# TP_IHM_7SEG.net
KiCad netlist of a schematic drawn in Altium Designer
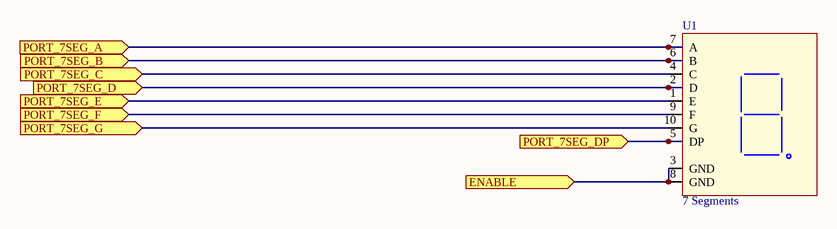
[diagram p0: TP_IHM_7SEG.SchDoc]

(export (version "E")
  (design (tool "Eeschema 10.0.6"))
  (components
    (comp (ref "U1")
      (value "7 Segments")
      (footprint "SA10-21GWA")
      (description "KingBright Led 7 Segments")
      (libsource (lib "TpGiven") (part "SC10-21SRWA"))
    )
  )
  (nets
    (net (code "1") (name "/ENABLE") (class "Default")
      (node (ref "U1") (pin "3") (pinfunction "GND_3") (pintype "passive"))
      (node (ref "U1") (pin "8") (pinfunction "GND_8") (pintype "passive"))
    )
    (net (code "2") (name "/PORT_7SEG_A") (class "Default")
      (node (ref "U1") (pin "7") (pinfunction "A_7") (pintype "passive"))
    )
    (net (code "3") (name "/PORT_7SEG_B") (class "Default")
      (node (ref "U1") (pin "6") (pinfunction "B_6") (pintype "passive"))
    )
    (net (code "4") (name "/PORT_7SEG_C") (class "Default")
      (node (ref "U1") (pin "4") (pinfunction "C_4") (pintype "passive"))
    )
    (net (code "5") (name "/PORT_7SEG_D") (class "Default")
      (node (ref "U1") (pin "2") (pinfunction "D_2") (pintype "passive"))
    )
    (net (code "6") (name "/PORT_7SEG_DP") (class "Default")
      (node (ref "U1") (pin "5") (pinfunction "DP_5") (pintype "passive"))
    )
    (net (code "7") (name "/PORT_7SEG_E") (class "Default")
      (node (ref "U1") (pin "1") (pinfunction "E_1") (pintype "passive"))
    )
    (net (code "8") (name "/PORT_7SEG_F") (class "Default")
      (node (ref "U1") (pin "9") (pinfunction "F_9") (pintype "passive"))
    )
    (net (code "9") (name "/PORT_7SEG_G") (class "Default")
      (node (ref "U1") (pin "10") (pinfunction "G_10") (pintype "passive"))
    )
  )
)
